# schema.net
KiCad netlist of a schematic drawn in EAGLE
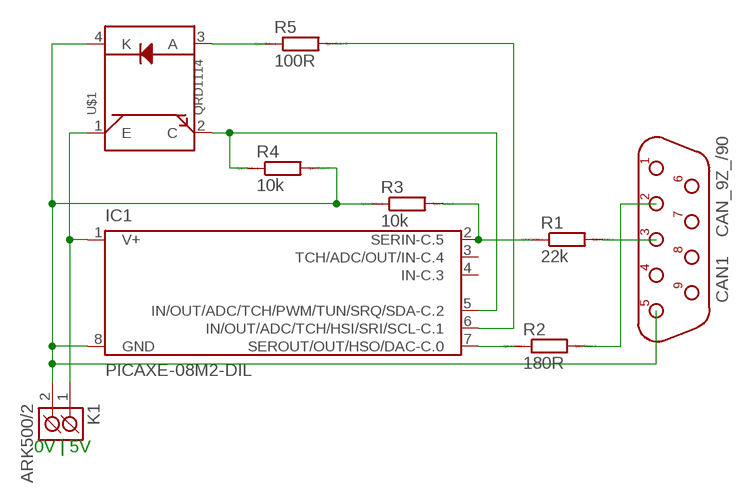
[diagram p0: schematic, sheet 1]

(export (version "E")
  (design (tool "Eeschema 10.0.6"))
  (components
    (comp (ref "CAN1")
      (value "CAN_9Z_/90")
      (footprint "eagle-import:CAN9Z_90")
      (libsource (lib "eagle-import") (part "CAN_9Z_/90"))
    )
    (comp (ref "IC1")
      (value "PICAXE-08M2-DIL")
      (footprint "eagle-import:DIL8")
      (libsource (lib "eagle-import") (part "PICAXE-08M2-DIL"))
    )
    (comp (ref "K1")
      (value "ARK500/2")
      (footprint "eagle-import:ARK500_2")
      (libsource (lib "eagle-import") (part "ARK500/2"))
    )
    (comp (ref "R1")
      (value "22k")
      (footprint "eagle-import:0207_10")
      (libsource (lib "eagle-import") (part "R0207/10"))
    )
    (comp (ref "R2")
      (value "180R")
      (footprint "eagle-import:0207_10")
      (libsource (lib "eagle-import") (part "R0207/10"))
    )
    (comp (ref "R3")
      (value "10k")
      (footprint "eagle-import:0207_10")
      (libsource (lib "eagle-import") (part "R0207/10"))
    )
    (comp (ref "R4")
      (value "10k")
      (footprint "eagle-import:0207_10")
      (libsource (lib "eagle-import") (part "R0207/10"))
    )
    (comp (ref "R5")
      (value "100R")
      (footprint "eagle-import:0207_10")
      (libsource (lib "eagle-import") (part "R0207/10"))
    )
    (comp (ref "U$1")
      (value "QRD1114")
      (footprint "eagle-import:QRD1114")
      (libsource (lib "eagle-import") (part "QRD1114"))
    )
  )
  (nets
    (net (code "1") (name "Net-(CAN1-Pad2)") (class "Default")
      (node (ref "CAN1") (pin "2") (pinfunction "2_2") (pintype "passive"))
      (node (ref "R2") (pin "2") (pinfunction "2_2") (pintype "passive"))
    )
    (net (code "2") (name "Net-(CAN1-Pad3)") (class "Default")
      (node (ref "CAN1") (pin "3") (pinfunction "3_3") (pintype "passive"))
      (node (ref "R1") (pin "2") (pinfunction "2_2") (pintype "passive"))
    )
    (net (code "3") (name "Net-(IC1-GND)") (class "Default")
      (node (ref "CAN1") (pin "5") (pinfunction "5_5") (pintype "passive"))
      (node (ref "IC1") (pin "8") (pinfunction "GND_8") (pintype "power_in"))
      (node (ref "K1") (pin "2") (pinfunction "K2_2") (pintype "passive"))
      (node (ref "R3") (pin "1") (pinfunction "1_1") (pintype "passive"))
      (node (ref "R4") (pin "2") (pinfunction "2_2") (pintype "passive"))
      (node (ref "U$1") (pin "4") (pinfunction "K_4") (pintype "bidirectional"))
    )
    (net (code "4") (name "Net-(IC1-IN{slash}OUT{slash}ADC{slash}TCH{slash}HSI{slash}SRI{slash}SCL-C.1)") (class "Default")
      (node (ref "IC1") (pin "6") (pinfunction "IN/OUT/ADC/TCH/HSI/SRI/SCL-C.1_6") (pintype "bidirectional"))
      (node (ref "R5") (pin "2") (pinfunction "2_2") (pintype "passive"))
    )
    (net (code "5") (name "Net-(IC1-IN{slash}OUT{slash}ADC{slash}TCH{slash}PWM{slash}TUN{slash}SRQ{slash}SDA-C.2)") (class "Default")
      (node (ref "IC1") (pin "5") (pinfunction "IN/OUT/ADC/TCH/PWM/TUN/SRQ/SDA-C.2_5") (pintype "bidirectional"))
      (node (ref "R4") (pin "1") (pinfunction "1_1") (pintype "passive"))
      (node (ref "U$1") (pin "2") (pinfunction "C_2") (pintype "bidirectional"))
    )
    (net (code "6") (name "Net-(IC1-SERIN-C.5)") (class "Default")
      (node (ref "IC1") (pin "2") (pinfunction "SERIN-C.5_2") (pintype "input"))
      (node (ref "R1") (pin "1") (pinfunction "1_1") (pintype "passive"))
      (node (ref "R3") (pin "2") (pinfunction "2_2") (pintype "passive"))
    )
    (net (code "7") (name "Net-(IC1-SEROUT{slash}OUT{slash}HSO{slash}DAC-C.0)") (class "Default")
      (node (ref "IC1") (pin "7") (pinfunction "SEROUT/OUT/HSO/DAC-C.0_7") (pintype "output"))
      (node (ref "R2") (pin "1") (pinfunction "1_1") (pintype "passive"))
    )
    (net (code "8") (name "Net-(IC1-V+)") (class "Default")
      (node (ref "IC1") (pin "1") (pinfunction "V+_1") (pintype "power_in"))
      (node (ref "K1") (pin "1") (pinfunction "K1_1") (pintype "passive"))
      (node (ref "U$1") (pin "1") (pinfunction "E_1") (pintype "bidirectional"))
    )
    (net (code "9") (name "Net-(U$1-A)") (class "Default")
      (node (ref "R5") (pin "1") (pinfunction "1_1") (pintype "passive"))
      (node (ref "U$1") (pin "3") (pinfunction "A_3") (pintype "bidirectional"))
    )
    (net (code "10") (name "unconnected-(CAN1-Pad1)") (class "Default")
      (node (ref "CAN1") (pin "1") (pinfunction "1_1") (pintype "passive"))
    )
    (net (code "11") (name "unconnected-(CAN1-Pad4)") (class "Default")
      (node (ref "CAN1") (pin "4") (pinfunction "4_4") (pintype "passive"))
    )
    (net (code "12") (name "unconnected-(CAN1-Pad6)") (class "Default")
      (node (ref "CAN1") (pin "6") (pinfunction "6_6") (pintype "passive"))
    )
    (net (code "13") (name "unconnected-(CAN1-Pad7)") (class "Default")
      (node (ref "CAN1") (pin "7") (pinfunction "7_7") (pintype "passive"))
    )
    (net (code "14") (name "unconnected-(CAN1-Pad8)") (class "Default")
      (node (ref "CAN1") (pin "8") (pinfunction "8_8") (pintype "passive"))
    )
    (net (code "15") (name "unconnected-(CAN1-Pad9)") (class "Default")
      (node (ref "CAN1") (pin "9") (pinfunction "9_9") (pintype "passive"))
    )
    (net (code "16") (name "unconnected-(IC1-IN-C.3-Pad4)") (class "Default")
      (node (ref "IC1") (pin "4") (pinfunction "IN-C.3_4") (pintype "input"))
    )
    (net (code "17") (name "unconnected-(IC1-TCH{slash}ADC{slash}OUT{slash}IN-C.4-Pad3)") (class "Default")
      (node (ref "IC1") (pin "3") (pinfunction "TCH/ADC/OUT/IN-C.4_3") (pintype "bidirectional"))
    )
  )
)
